# Analog_Mux.net
KiCad netlist of a schematic drawn in Altium Designer
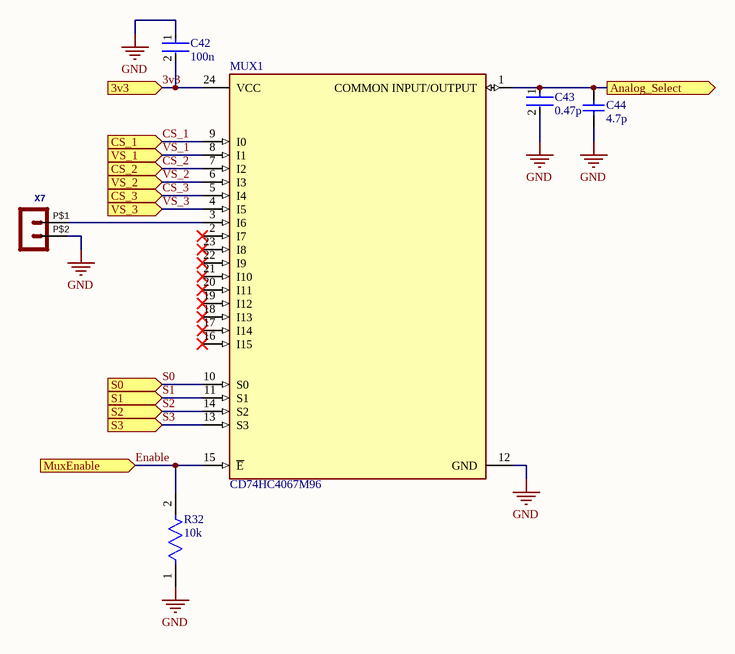
[diagram p0: Analog_Mux.SchDoc]

(export (version "E")
  (design (tool "Eeschema 10.0.6"))
  (components
    (comp (ref "C42")
      (value "100n")
      (footprint "FP-CGA3E-0_3-0_1-IPC_A")
      (description "Cap Ceramic 100nF 50V X7R 10% Pad SMD 0603 +125°C Automotive T/R")
      (fields (field (name "TOLERANCE") "10%") (field (name "VOLTAGE") "50V"))
      (libsource (lib "Altium Content Vault") (part "b4654b650e69147ec39a6b967a45e02"))
    )
    (comp (ref "C43")
      (value "0.47p")
      (footprint "FP-CL21-IPC_B")
      (description "CL21 Series 0805 0.47pF 50V ±0.1pF Tolerance C0G Multilayer Ceramic Chip Capacitor")
      (fields (field (name "VOLTAGE") "50V"))
      (libsource (lib "Altium Content Vault") (part "b4654b650e69147ec39a6b967a45e02"))
    )
    (comp (ref "C44")
      (value "4.7p")
      (footprint "CAPC1608X90X35ML10T15")
      (fields (field (name "PART NUMBER") "GRM1885C1H4R7CA01D") (field (name "MANUFACTURER") "Murata"))
      (libsource (lib "Altium Content Vault") (part "CAP"))
    )
    (comp (ref "MUX1")
      (value "CD74HC4067M96")
      (footprint "FP-DW0024A-MFG")
      (description "IC MUX/DEMUX 1X16 24SOIC")
      (fields
        (field (name "OCTOPART") "https://octopart.com/cd74hc4067m96-texas+instruments-722802")
        (field (name "MANUFACTURER") "Texas Instruments")
      )
      (libsource (lib "Altium Content Vault") (part "0e3014a41e7f600214dac1b4fa06845"))
    )
    (comp (ref "R32")
      (value "10k")
      (footprint "FP-RC0603-0_55-IPC_C")
      (description "RES 10K OHM 1% 1/10W 0603")
      (fields (field (name "TOLERANCE") "1%"))
      (libsource (lib "Altium Content Vault") (part "1029c3af85768c4190bb7ad29bc67b5"))
    )
    (comp (ref "X7")
      (value "Molex - Micro-Fit 3.0 Series connector,  3.00mm (0.118\") pitch header, 2 positions.")
      (footprint "44914-0201")
      (libsource (lib "Molex Microfit") (part "HEADER_POS2_?44914-0201"))
    )
  )
  (nets
    (net (code "1") (name "/3v3") (class "Default")
      (node (ref "C42") (pin "2") (pinfunction "2_2") (pintype "passive"))
      (node (ref "MUX1") (pin "24") (pinfunction "VCC_24") (pintype "power_in"))
    )
    (net (code "2") (name "/Analog_Select") (class "Default")
      (node (ref "C43") (pin "1") (pinfunction "1_1") (pintype "passive"))
      (node (ref "C44") (pin "2") (pinfunction "2_2") (pintype "passive"))
      (node (ref "MUX1") (pin "1") (pinfunction "COMMON_INPUT/OUTPUT_1") (pintype "bidirectional"))
    )
    (net (code "3") (name "/CS_1") (class "Default")
      (node (ref "MUX1") (pin "9") (pinfunction "I0_9") (pintype "input"))
    )
    (net (code "4") (name "/CS_2") (class "Default")
      (node (ref "MUX1") (pin "7") (pinfunction "I2_7") (pintype "input"))
    )
    (net (code "5") (name "/CS_3") (class "Default")
      (node (ref "MUX1") (pin "5") (pinfunction "I4_5") (pintype "input"))
    )
    (net (code "6") (name "/Enable") (class "Default")
      (node (ref "MUX1") (pin "15") (pinfunction "~{E}_15") (pintype "input"))
      (node (ref "R32") (pin "2") (pinfunction "2_2") (pintype "passive"))
    )
    (net (code "7") (name "/S0") (class "Default")
      (node (ref "MUX1") (pin "10") (pinfunction "S0_10") (pintype "input"))
    )
    (net (code "8") (name "/S1") (class "Default")
      (node (ref "MUX1") (pin "11") (pinfunction "S1_11") (pintype "input"))
    )
    (net (code "9") (name "/S2") (class "Default")
      (node (ref "MUX1") (pin "14") (pinfunction "S2_14") (pintype "input"))
    )
    (net (code "10") (name "/S3") (class "Default")
      (node (ref "MUX1") (pin "13") (pinfunction "S3_13") (pintype "input"))
    )
    (net (code "11") (name "/VS_1") (class "Default")
      (node (ref "MUX1") (pin "8") (pinfunction "I1_8") (pintype "input"))
    )
    (net (code "12") (name "/VS_2") (class "Default")
      (node (ref "MUX1") (pin "6") (pinfunction "I3_6") (pintype "input"))
    )
    (net (code "13") (name "/VS_3") (class "Default")
      (node (ref "MUX1") (pin "4") (pinfunction "I5_4") (pintype "input"))
    )
    (net (code "14") (name "GND") (class "Default")
      (node (ref "C42") (pin "1") (pinfunction "1_1") (pintype "passive"))
      (node (ref "C43") (pin "2") (pinfunction "2_2") (pintype "passive"))
      (node (ref "C44") (pin "1") (pinfunction "1_1") (pintype "passive"))
      (node (ref "MUX1") (pin "12") (pinfunction "GND_12") (pintype "power_in"))
      (node (ref "R32") (pin "1") (pinfunction "1_1") (pintype "passive"))
      (node (ref "X7") (pin "P$2") (pinfunction "2_P$2") (pintype "passive"))
    )
    (net (code "15") (name "Net-(MUX1-I6)") (class "Default")
      (node (ref "MUX1") (pin "3") (pinfunction "I6_3") (pintype "input"))
      (node (ref "X7") (pin "P$1") (pinfunction "1_P$1") (pintype "passive"))
    )
    (net (code "16") (name "unconnected-(MUX1-I7-Pad2)") (class "Default")
      (node (ref "MUX1") (pin "2") (pinfunction "I7_2") (pintype "input+no_connect"))
    )
    (net (code "17") (name "unconnected-(MUX1-I8-Pad23)") (class "Default")
      (node (ref "MUX1") (pin "23") (pinfunction "I8_23") (pintype "input+no_connect"))
    )
    (net (code "18") (name "unconnected-(MUX1-I9-Pad22)") (class "Default")
      (node (ref "MUX1") (pin "22") (pinfunction "I9_22") (pintype "input+no_connect"))
    )
    (net (code "19") (name "unconnected-(MUX1-I10-Pad21)") (class "Default")
      (node (ref "MUX1") (pin "21") (pinfunction "I10_21") (pintype "input+no_connect"))
    )
    (net (code "20") (name "unconnected-(MUX1-I11-Pad20)") (class "Default")
      (node (ref "MUX1") (pin "20") (pinfunction "I11_20") (pintype "input+no_connect"))
    )
    (net (code "21") (name "unconnected-(MUX1-I12-Pad19)") (class "Default")
      (node (ref "MUX1") (pin "19") (pinfunction "I12_19") (pintype "input+no_connect"))
    )
    (net (code "22") (name "unconnected-(MUX1-I13-Pad18)") (class "Default")
      (node (ref "MUX1") (pin "18") (pinfunction "I13_18") (pintype "input+no_connect"))
    )
    (net (code "23") (name "unconnected-(MUX1-I14-Pad17)") (class "Default")
      (node (ref "MUX1") (pin "17") (pinfunction "I14_17") (pintype "input+no_connect"))
    )
    (net (code "24") (name "unconnected-(MUX1-I15-Pad16)") (class "Default")
      (node (ref "MUX1") (pin "16") (pinfunction "I15_16") (pintype "input+no_connect"))
    )
  )
)
